# Hex-Inverter1.net
KiCad netlist of a schematic drawn in Altium Designer
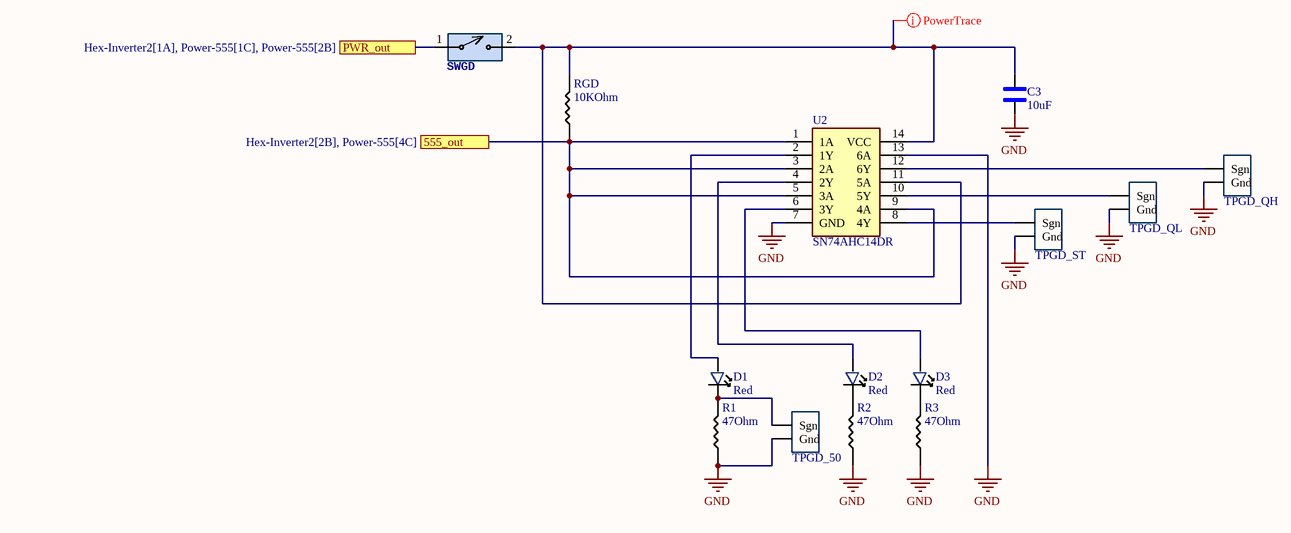
[diagram p0: Hex-Inverter1.SchDoc]

(export (version "E")
  (design (tool "Eeschema 10.0.6"))
  (components
    (comp (ref "C3")
      (value "10uF")
      (footprint "1206_Passive_Capacitor")
      (description "10uF ±10% 50V X5R 1206 Multilayer Ceramic Capacitors MLCC - SMD/SMT RoHS")
      (fields (field (name "LCSC PART#") "C13585") (field (name "MFR PART #") "CL31A106KBHNNNE"))
      (libsource (lib "ECEN5730Lib") (part "C_10uF_1206"))
    )
    (comp (ref "D1")
      (value "Red")
      (footprint "LED_1206")
      (description "Red 621~631nm 1206 Light Emitting Diodes (LED) RoHS")
      (fields (field (name "MFR PART #") "15-21/R6C-FQ1R1B/2T") (field (name "LCSC PART#") "C93133"))
      (libsource (lib "ECEN5730Lib") (part "LED_RED_1206"))
    )
    (comp (ref "D2")
      (value "Red")
      (footprint "LED_1206")
      (description "Red 621~631nm 1206 Light Emitting Diodes (LED) RoHS")
      (fields (field (name "MFR PART #") "15-21/R6C-FQ1R1B/2T") (field (name "LCSC PART#") "C93133"))
      (libsource (lib "ECEN5730Lib") (part "LED_RED_1206"))
    )
    (comp (ref "D3")
      (value "Red")
      (footprint "LED_1206")
      (description "Red 621~631nm 1206 Light Emitting Diodes (LED) RoHS")
      (fields (field (name "MFR PART #") "15-21/R6C-FQ1R1B/2T") (field (name "LCSC PART#") "C93133"))
      (libsource (lib "ECEN5730Lib") (part "LED_RED_1206"))
    )
    (comp (ref "R1")
      (value "47Ohm")
      (footprint "1206_Passive_Resitor")
      (description "47Ω ±5% 0.25W ±200ppm/℃ 1206 Chip Resistor - Surface Mount RoHS")
      (fields (field (name "MFR PART #") "1206W4J0470T5E") (field (name "LCSC PART#") "C25384"))
      (libsource (lib "ECEN5730Lib") (part "R_47Ohm_1206"))
    )
    (comp (ref "R2")
      (value "47Ohm")
      (footprint "1206_Passive_Resitor")
      (description "47Ω ±5% 0.25W ±200ppm/℃ 1206 Chip Resistor - Surface Mount RoHS")
      (fields (field (name "MFR PART #") "1206W4J0470T5E") (field (name "LCSC PART#") "C25384"))
      (libsource (lib "ECEN5730Lib") (part "R_47Ohm_1206"))
    )
    (comp (ref "R3")
      (value "47Ohm")
      (footprint "1206_Passive_Resitor")
      (description "47Ω ±5% 0.25W ±200ppm/℃ 1206 Chip Resistor - Surface Mount RoHS")
      (fields (field (name "MFR PART #") "1206W4J0470T5E") (field (name "LCSC PART#") "C25384"))
      (libsource (lib "ECEN5730Lib") (part "R_47Ohm_1206"))
    )
    (comp (ref "RGD")
      (value "10KOhm")
      (footprint "1206_Passive_Resitor")
      (description "10 kOhms ±5% 0.25W, 1/4W Chip Resistor 1206 (3216 Metric) Automotive AEC-Q200 Thick Film")
      (fields (field (name "MFR PART #") "RMCF1206FT10K0") (field (name "LCSC PART#") "C17902"))
      (libsource (lib "ECEN5730Lib") (part "R_10KOhm_1206"))
    )
    (comp (ref "SWGD")
      (value "SW_2Pin_100mil_Switch")
      (footprint "2Pin-Header-Conn")
      (description "2Pin Header")
      (fields (field (name "LCSC PART#") "C124375"))
      (libsource (lib "ECEN5730Lib") (part "SW_2Pin_100mil_Switch"))
    )
    (comp (ref "TPGD_50")
      (value "10x Probe TP")
      (footprint "TP10x_Probe")
      (description "Test Point 300 mil centers")
      (libsource (lib "ECEN5730Lib") (part "TP_10x_Probe"))
    )
    (comp (ref "TPGD_QH")
      (value "10x Probe TP")
      (footprint "TP10x_Probe")
      (description "Test Point 300 mil centers")
      (libsource (lib "ECEN5730Lib") (part "TP_10x_Probe"))
    )
    (comp (ref "TPGD_QL")
      (value "10x Probe TP")
      (footprint "TP10x_Probe")
      (description "Test Point 300 mil centers")
      (libsource (lib "ECEN5730Lib") (part "TP_10x_Probe"))
    )
    (comp (ref "TPGD_ST")
      (value "10x Probe TP")
      (footprint "TP10x_Probe")
      (description "Test Point 300 mil centers")
      (libsource (lib "ECEN5730Lib") (part "TP_10x_Probe"))
    )
    (comp (ref "U2")
      (value "SN74AHC14DR")
      (footprint "HEX_74AC14")
      (description "Inverter IC 6 Channel Schmitt Trigger 14-SOIC")
      (fields (field (name "LCSC PART#") "C6942"))
      (libsource (lib "ECEN5730Lib") (part "U_74AHC14"))
    )
  )
  (nets
    (net (code "1") (name "/555_out") (class "Default")
      (node (ref "RGD") (pin "1") (pinfunction "1_1") (pintype "passive"))
      (node (ref "U2") (pin "1") (pinfunction "1A_1") (pintype "passive"))
      (node (ref "U2") (pin "3") (pinfunction "2A_3") (pintype "passive"))
      (node (ref "U2") (pin "5") (pinfunction "3A_5") (pintype "passive"))
      (node (ref "U2") (pin "9") (pinfunction "4A_9") (pintype "passive"))
    )
    (net (code "2") (name "/PWR_out") (class "Default")
      (node (ref "SWGD") (pin "1") (pinfunction "1_1") (pintype "passive"))
    )
    (net (code "3") (name "GND") (class "Default")
      (node (ref "C3") (pin "1") (pinfunction "1_1") (pintype "passive"))
      (node (ref "R1") (pin "1") (pinfunction "1_1") (pintype "passive"))
      (node (ref "R2") (pin "1") (pinfunction "1_1") (pintype "passive"))
      (node (ref "R3") (pin "1") (pinfunction "1_1") (pintype "passive"))
      (node (ref "TPGD_50") (pin "2") (pinfunction "Gnd_2") (pintype "passive"))
      (node (ref "TPGD_QH") (pin "2") (pinfunction "Gnd_2") (pintype "passive"))
      (node (ref "TPGD_QL") (pin "2") (pinfunction "Gnd_2") (pintype "passive"))
      (node (ref "TPGD_ST") (pin "2") (pinfunction "Gnd_2") (pintype "passive"))
      (node (ref "U2") (pin "13") (pinfunction "6A_13") (pintype "passive"))
      (node (ref "U2") (pin "7") (pinfunction "GND_7") (pintype "passive"))
    )
    (net (code "4") (name "Net-(D2-Pad2)") (class "Default")
      (node (ref "D2") (pin "2") (pinfunction "2_2") (pintype "passive"))
      (node (ref "R2") (pin "2") (pinfunction "2_2") (pintype "passive"))
    )
    (net (code "5") (name "Net-(D3-Pad2)") (class "Default")
      (node (ref "D3") (pin "2") (pinfunction "2_2") (pintype "passive"))
      (node (ref "R3") (pin "2") (pinfunction "2_2") (pintype "passive"))
    )
    (net (code "6") (name "Net-(TPGD_50-Sgn)") (class "Default")
      (node (ref "D1") (pin "2") (pinfunction "2_2") (pintype "passive"))
      (node (ref "R1") (pin "2") (pinfunction "2_2") (pintype "passive"))
      (node (ref "TPGD_50") (pin "1") (pinfunction "Sgn_1") (pintype "passive"))
    )
    (net (code "7") (name "Net-(TPGD_QH-Sgn)") (class "Default")
      (node (ref "TPGD_QH") (pin "1") (pinfunction "Sgn_1") (pintype "passive"))
      (node (ref "U2") (pin "12") (pinfunction "6Y_12") (pintype "passive"))
    )
    (net (code "8") (name "Net-(TPGD_QL-Sgn)") (class "Default")
      (node (ref "TPGD_QL") (pin "1") (pinfunction "Sgn_1") (pintype "passive"))
      (node (ref "U2") (pin "10") (pinfunction "5Y_10") (pintype "passive"))
    )
    (net (code "9") (name "Net-(TPGD_ST-Sgn)") (class "Default")
      (node (ref "TPGD_ST") (pin "1") (pinfunction "Sgn_1") (pintype "passive"))
      (node (ref "U2") (pin "8") (pinfunction "4Y_8") (pintype "passive"))
    )
    (net (code "10") (name "Net-(U2-1Y)") (class "Default")
      (node (ref "D1") (pin "1") (pinfunction "1_1") (pintype "passive"))
      (node (ref "U2") (pin "2") (pinfunction "1Y_2") (pintype "passive"))
    )
    (net (code "11") (name "Net-(U2-2Y)") (class "Default")
      (node (ref "D2") (pin "1") (pinfunction "1_1") (pintype "passive"))
      (node (ref "U2") (pin "4") (pinfunction "2Y_4") (pintype "passive"))
    )
    (net (code "12") (name "Net-(U2-3Y)") (class "Default")
      (node (ref "D3") (pin "1") (pinfunction "1_1") (pintype "passive"))
      (node (ref "U2") (pin "6") (pinfunction "3Y_6") (pintype "passive"))
    )
    (net (code "13") (name "Net-(U2-5A)") (class "Default")
      (node (ref "C3") (pin "2") (pinfunction "2_2") (pintype "passive"))
      (node (ref "RGD") (pin "2") (pinfunction "2_2") (pintype "passive"))
      (node (ref "SWGD") (pin "2") (pinfunction "2_2") (pintype "passive"))
      (node (ref "U2") (pin "11") (pinfunction "5A_11") (pintype "passive"))
      (node (ref "U2") (pin "14") (pinfunction "VCC_14") (pintype "passive"))
    )
  )
)
